# Gastroscopy-Controller_Button.net
KiCad netlist of a schematic drawn in Altium Designer
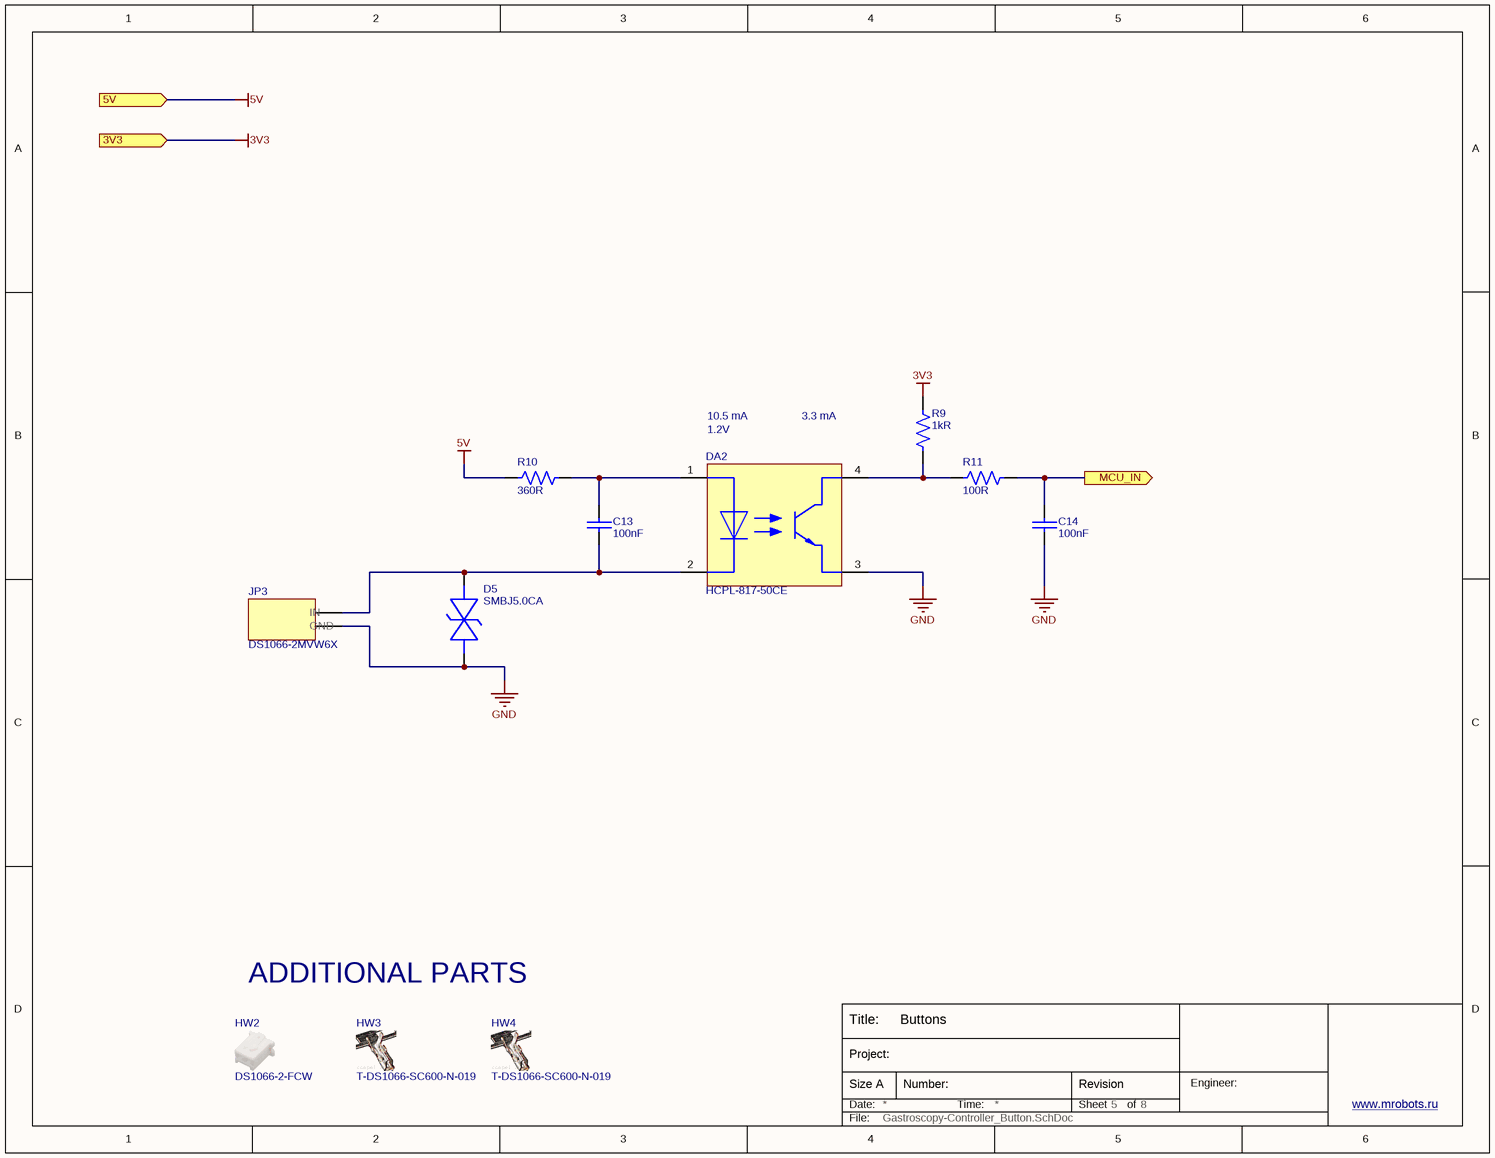
[diagram p0: Gastroscopy-Controller_Button.SchDoc]

(export (version "E")
  (design (tool "Eeschema 10.0.6"))
  (components
    (comp (ref "C13")
      (value "100nF")
      (footprint "CAP_0603")
      (description "CAP CER 0.1UF 50V X7R 0603")
      (fields (field (name "TOLERANCE") "10%"))
      (libsource (lib "Gastroscopy-Controller") (part "CL10B104KB8NNNL"))
    )
    (comp (ref "C14")
      (value "100nF")
      (footprint "CAP_0603")
      (description "CAP CER 0.1UF 50V X7R 0603")
      (fields (field (name "TOLERANCE") "10%"))
      (libsource (lib "Gastroscopy-Controller") (part "CL10B104KB8NNNL"))
    )
    (comp (ref "D5")
      (value "SMBJ5.0CA")
      (footprint "SMB-BIDIR")
      (description "TVS DIODE 5VWM 9.2VC SMB")
      (libsource (lib "Gastroscopy-Controller") (part "SMBJ5.0CA"))
    )
    (comp (ref "DA2")
      (value "HCPL-817-50CE")
      (footprint "HCPL-817-50CE")
      (description "OPTOISOLATOR 5KV TRANSISTOR 4SMD")
      (libsource (lib "Gastroscopy-Controller") (part "HCPL-817-50CE"))
    )
    (comp (ref "HW2")
      (value "DS1066-2-FCW")
      (description "CONN SOCKET 2POS 2MM")
      (libsource (lib "Gastroscopy-Controller") (part "DS1066-2-FCW"))
    )
    (comp (ref "HW3")
      (value "T-DS1066-SC600-N-019")
      (description "СONNECTOR DS1066")
      (libsource (lib "Gastroscopy-Controller") (part "T-DS1066-SC600-N-019"))
    )
    (comp (ref "HW4")
      (value "T-DS1066-SC600-N-019")
      (description "СONNECTOR DS1066")
      (libsource (lib "Gastroscopy-Controller") (part "T-DS1066-SC600-N-019"))
    )
    (comp (ref "JP3")
      (value "DS1066-2MVW6X")
      (footprint "DS1066-2MVW6X")
      (description "CONN HEADER 2POS 2MM")
      (libsource (lib "Gastroscopy-Controller") (part "DS1066-2MVW6X"))
    )
    (comp (ref "R9")
      (value "1kR")
      (footprint "RES_0603")
      (description "RES 1K OHM 1% 1/10W 0603")
      (fields (field (name "TOLERANCE") "1%"))
      (libsource (lib "Gastroscopy-Controller") (part "RC0603FR-071KL"))
    )
    (comp (ref "R10")
      (value "360R")
      (footprint "RES_0603")
      (description "RES 360 OHM 1% 1/10W 0603")
      (fields (field (name "TOLERANCE") "1%"))
      (libsource (lib "Gastroscopy-Controller") (part "RC0603FR-07360RL"))
    )
    (comp (ref "R11")
      (value "100R")
      (footprint "RES_0603")
      (description "RES 100 OHM 1% 1/10W 0603")
      (fields (field (name "TOLERANCE") "1%"))
      (libsource (lib "Gastroscopy-Controller") (part "RC0603FR-07100RL"))
    )
  )
  (nets
    (net (code "1") (name "/MCU_IN") (class "Default")
      (node (ref "C14") (pin "1") (pinfunction "1_1") (pintype "passive"))
      (node (ref "R11") (pin "1") (pinfunction "1_1") (pintype "passive"))
    )
    (net (code "2") (name "3V3") (class "Default")
      (node (ref "R9") (pin "1") (pinfunction "1_1") (pintype "passive"))
    )
    (net (code "3") (name "5V") (class "Default")
      (node (ref "R10") (pin "1") (pinfunction "1_1") (pintype "passive"))
    )
    (net (code "4") (name "GND") (class "Default")
      (node (ref "C14") (pin "2") (pinfunction "2_2") (pintype "passive"))
      (node (ref "D5") (pin "2") (pinfunction "2_2") (pintype "passive"))
      (node (ref "DA2") (pin "3") (pinfunction "EMITTER_3") (pintype "passive"))
      (node (ref "JP3") (pin "2") (pinfunction "2_2") (pintype "passive"))
    )
    (net (code "5") (name "Net-(DA2-ANODE)") (class "Default")
      (node (ref "C13") (pin "1") (pinfunction "1_1") (pintype "passive"))
      (node (ref "DA2") (pin "1") (pinfunction "ANODE_1") (pintype "passive"))
      (node (ref "R10") (pin "2") (pinfunction "2_2") (pintype "passive"))
    )
    (net (code "6") (name "Net-(DA2-CATHODE)") (class "Default")
      (node (ref "C13") (pin "2") (pinfunction "2_2") (pintype "passive"))
      (node (ref "D5") (pin "1") (pinfunction "1_1") (pintype "passive"))
      (node (ref "DA2") (pin "2") (pinfunction "CATHODE_2") (pintype "passive"))
      (node (ref "JP3") (pin "1") (pinfunction "1_1") (pintype "passive"))
    )
    (net (code "7") (name "Net-(DA2-COLLECTOR)") (class "Default")
      (node (ref "DA2") (pin "4") (pinfunction "COLLECTOR_4") (pintype "passive"))
      (node (ref "R11") (pin "2") (pinfunction "2_2") (pintype "passive"))
      (node (ref "R9") (pin "2") (pinfunction "2_2") (pintype "passive"))
    )
  )
)
